# ChessComputer.net
KiCad netlist of a schematic drawn in EAGLE
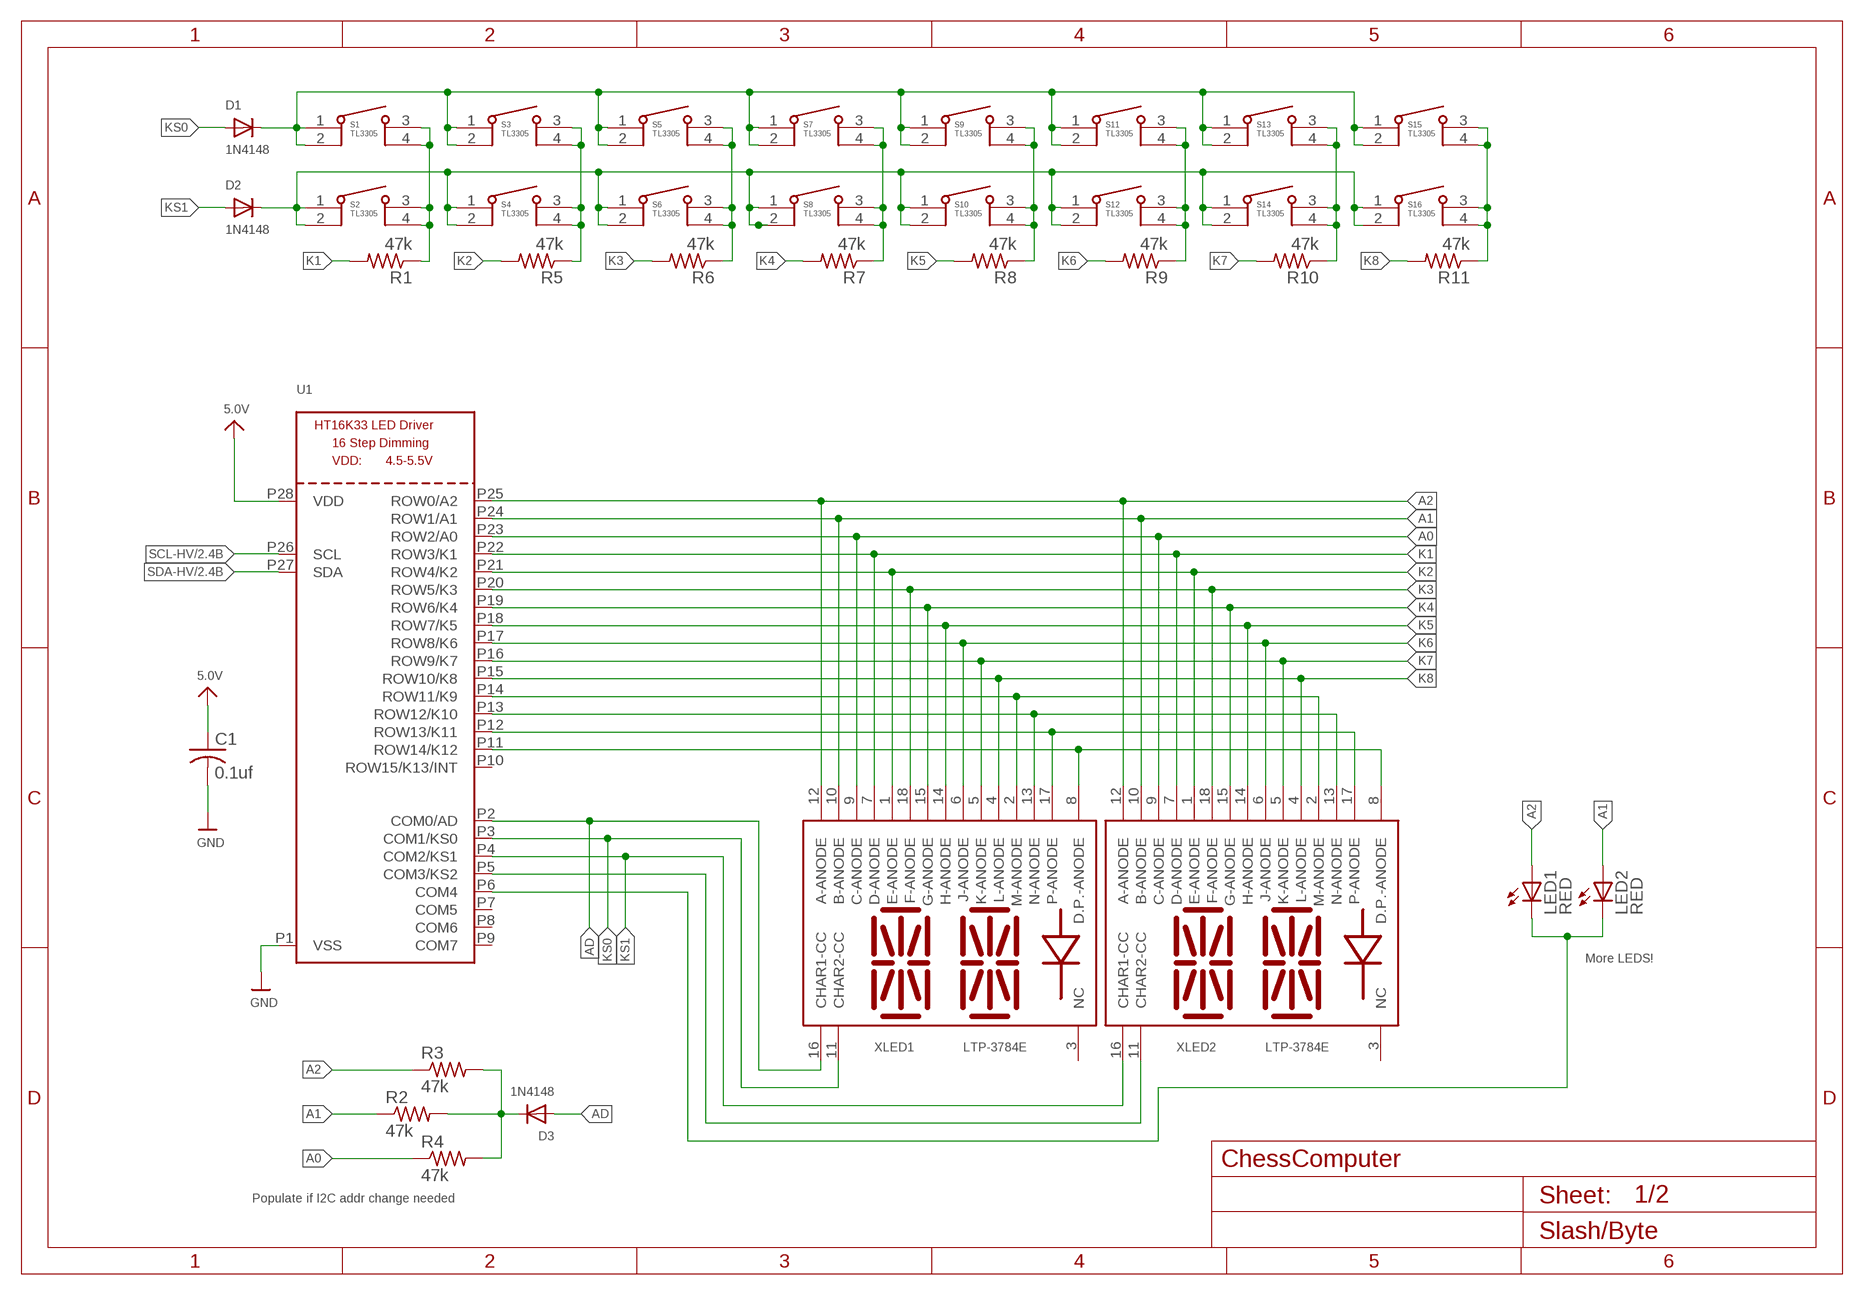
[diagram p0: schematic, sheet 1]
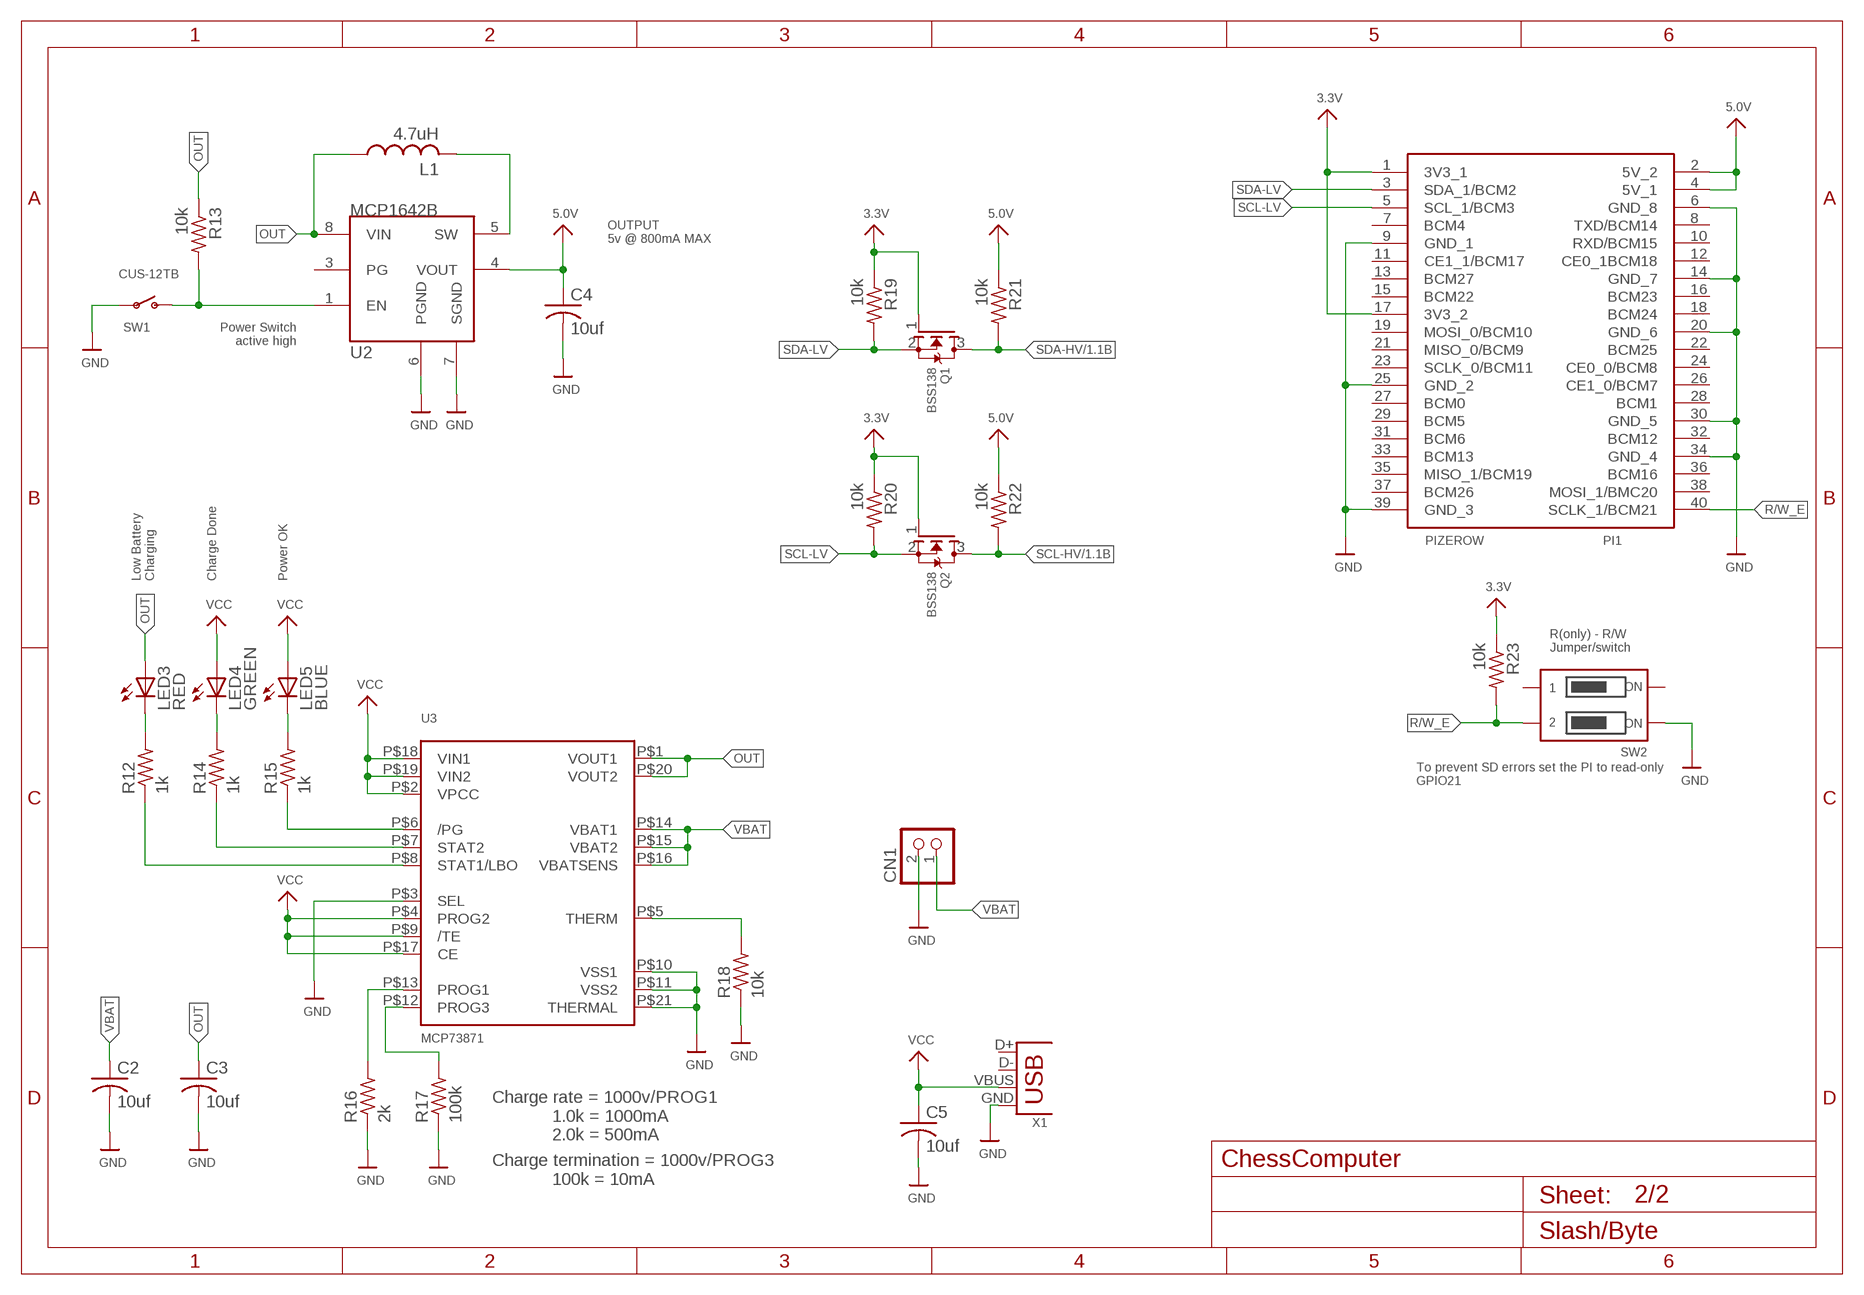
[diagram p1: schematic, sheet 2]

(export (version "E")
  (design (tool "Eeschema 10.0.6"))
  (components
    (comp (ref "C2")
      (value "10uf")
      (footprint "eagle-import:C0805K")
      (libsource (lib "eagle-import") (part "C-USC0805K"))
    )
    (comp (ref "C3")
      (value "10uf")
      (footprint "eagle-import:C0805K")
      (libsource (lib "eagle-import") (part "C-USC0805K"))
    )
    (comp (ref "C4")
      (value "10uf")
      (footprint "eagle-import:C0805K")
      (libsource (lib "eagle-import") (part "C-USC0805K"))
    )
    (comp (ref "C5")
      (value "10uf")
      (footprint "eagle-import:C0805K")
      (libsource (lib "eagle-import") (part "C-USC0805K"))
    )
    (comp (ref "CN1")
      (value "JST_2PIN-SMT-RA")
      (footprint "eagle-import:JST-PH-2-SMT-RA")
      (libsource (lib "eagle-import") (part "JST_2PIN-SMT-RA"))
    )
    (comp (ref "L1")
      (value "4.7uH")
      (footprint "eagle-import:TYS60204R7N-10")
      (libsource (lib "eagle-import") (part "TYS60204R7N-10"))
    )
    (comp (ref "LED3")
      (value "RED")
      (footprint "eagle-import:LED3MM")
      (libsource (lib "eagle-import") (part "LED3MM"))
    )
    (comp (ref "LED4")
      (value "GREEN")
      (footprint "eagle-import:LED3MM")
      (libsource (lib "eagle-import") (part "LED3MM"))
    )
    (comp (ref "LED5")
      (value "BLUE")
      (footprint "eagle-import:LED3MM")
      (libsource (lib "eagle-import") (part "LED3MM"))
    )
    (comp (ref "PI1")
      (value "PIZEROW")
      (footprint "eagle-import:RASP_PI_ZERO_BOARD_FULL")
      (libsource (lib "eagle-import") (part "PIZEROW"))
    )
    (comp (ref "Q1")
      (value "BSS138")
      (footprint "eagle-import:SOT23-R")
      (libsource (lib "eagle-import") (part "MOSFET-NREFLOW"))
    )
    (comp (ref "Q2")
      (value "BSS138")
      (footprint "eagle-import:SOT23-R")
      (libsource (lib "eagle-import") (part "MOSFET-NREFLOW"))
    )
    (comp (ref "R12")
      (value "1k")
      (footprint "eagle-import:M0805")
      (libsource (lib "eagle-import") (part "R-US_M0805"))
    )
    (comp (ref "R13")
      (value "10k")
      (footprint "eagle-import:M0805")
      (libsource (lib "eagle-import") (part "R-US_M0805"))
    )
    (comp (ref "R14")
      (value "1k")
      (footprint "eagle-import:M0805")
      (libsource (lib "eagle-import") (part "R-US_M0805"))
    )
    (comp (ref "R15")
      (value "1k")
      (footprint "eagle-import:M0805")
      (libsource (lib "eagle-import") (part "R-US_M0805"))
    )
    (comp (ref "R16")
      (value "2k")
      (footprint "eagle-import:M0805")
      (libsource (lib "eagle-import") (part "R-US_M0805"))
    )
    (comp (ref "R17")
      (value "100k")
      (footprint "eagle-import:M0805")
      (libsource (lib "eagle-import") (part "R-US_M0805"))
    )
    (comp (ref "R18")
      (value "10k")
      (footprint "eagle-import:M0805")
      (libsource (lib "eagle-import") (part "R-US_M0805"))
    )
    (comp (ref "R19")
      (value "10k")
      (footprint "eagle-import:M0805")
      (libsource (lib "eagle-import") (part "R-US_M0805"))
    )
    (comp (ref "R20")
      (value "10k")
      (footprint "eagle-import:M0805")
      (libsource (lib "eagle-import") (part "R-US_M0805"))
    )
    (comp (ref "R21")
      (value "10k")
      (footprint "eagle-import:M0805")
      (libsource (lib "eagle-import") (part "R-US_M0805"))
    )
    (comp (ref "R22")
      (value "10k")
      (footprint "eagle-import:M0805")
      (libsource (lib "eagle-import") (part "R-US_M0805"))
    )
    (comp (ref "R23")
      (value "10k")
      (footprint "eagle-import:M0805")
      (libsource (lib "eagle-import") (part "R-US_M0805"))
    )
    (comp (ref "SW1")
      (value "CUS-12TB")
      (footprint "eagle-import:SPST_SMT_19192")
      (libsource (lib "eagle-import") (part "SWITCH_SPST"))
    )
    (comp (ref "SW2")
      (value "DIPSWITCH_2PIN")
      (footprint "eagle-import:DIPSWITCH_2PIN")
      (libsource (lib "eagle-import") (part "DIPSWITCH_2PIN"))
    )
    (comp (ref "U2")
      (value "MCP1642B")
      (footprint "eagle-import:MSOP8")
      (libsource (lib "eagle-import") (part "MCP1642B"))
    )
    (comp (ref "U3")
      (value "MCP73871")
      (footprint "eagle-import:QFN20_4MM")
      (libsource (lib "eagle-import") (part "MCP73871"))
    )
    (comp (ref "X1")
      (value "MICRO-USB_ORIG")
      (footprint "eagle-import:DX4R005HJ5")
      (libsource (lib "eagle-import") (part "MICRO-USB_ORIG"))
    )
    (comp (ref "C1")
      (value "0.1uf")
      (footprint "eagle-import:C0805K")
      (libsource (lib "eagle-import") (part "C-USC0805K"))
    )
    (comp (ref "D1")
      (value "1N4148")
      (footprint "eagle-import:SOD-523")
      (libsource (lib "eagle-import") (part "DIODESOD-523"))
    )
    (comp (ref "D2")
      (value "1N4148")
      (footprint "eagle-import:SOD-523")
      (libsource (lib "eagle-import") (part "DIODESOD-523"))
    )
    (comp (ref "D3")
      (value "1N4148")
      (footprint "eagle-import:SOD-523")
      (libsource (lib "eagle-import") (part "DIODESOD-523"))
    )
    (comp (ref "LED1")
      (value "RED")
      (footprint "eagle-import:LED3MM")
      (libsource (lib "eagle-import") (part "LED3MM"))
    )
    (comp (ref "LED2")
      (value "RED")
      (footprint "eagle-import:LED3MM")
      (libsource (lib "eagle-import") (part "LED3MM"))
    )
    (comp (ref "R1")
      (value "47k")
      (footprint "eagle-import:M0805")
      (libsource (lib "eagle-import") (part "R-US_M0805"))
    )
    (comp (ref "R2")
      (value "47k")
      (footprint "eagle-import:M0805")
      (libsource (lib "eagle-import") (part "R-US_M0805"))
    )
    (comp (ref "R3")
      (value "47k")
      (footprint "eagle-import:M0805")
      (libsource (lib "eagle-import") (part "R-US_M0805"))
    )
    (comp (ref "R4")
      (value "47k")
      (footprint "eagle-import:M0805")
      (libsource (lib "eagle-import") (part "R-US_M0805"))
    )
    (comp (ref "R5")
      (value "47k")
      (footprint "eagle-import:M0805")
      (libsource (lib "eagle-import") (part "R-US_M0805"))
    )
    (comp (ref "R6")
      (value "47k")
      (footprint "eagle-import:M0805")
      (libsource (lib "eagle-import") (part "R-US_M0805"))
    )
    (comp (ref "R7")
      (value "47k")
      (footprint "eagle-import:M0805")
      (libsource (lib "eagle-import") (part "R-US_M0805"))
    )
    (comp (ref "R8")
      (value "47k")
      (footprint "eagle-import:M0805")
      (libsource (lib "eagle-import") (part "R-US_M0805"))
    )
    (comp (ref "R9")
      (value "47k")
      (footprint "eagle-import:M0805")
      (libsource (lib "eagle-import") (part "R-US_M0805"))
    )
    (comp (ref "R10")
      (value "47k")
      (footprint "eagle-import:M0805")
      (libsource (lib "eagle-import") (part "R-US_M0805"))
    )
    (comp (ref "R11")
      (value "47k")
      (footprint "eagle-import:M0805")
      (libsource (lib "eagle-import") (part "R-US_M0805"))
    )
    (comp (ref "S1")
      (value "TL3305")
      (footprint "eagle-import:TL3305")
      (libsource (lib "eagle-import") (part "TL3305"))
    )
    (comp (ref "S2")
      (value "TL3305")
      (footprint "eagle-import:TL3305")
      (libsource (lib "eagle-import") (part "TL3305"))
    )
    (comp (ref "S3")
      (value "TL3305")
      (footprint "eagle-import:TL3305")
      (libsource (lib "eagle-import") (part "TL3305"))
    )
    (comp (ref "S4")
      (value "TL3305")
      (footprint "eagle-import:TL3305")
      (libsource (lib "eagle-import") (part "TL3305"))
    )
    (comp (ref "S5")
      (value "TL3305")
      (footprint "eagle-import:TL3305")
      (libsource (lib "eagle-import") (part "TL3305"))
    )
    (comp (ref "S6")
      (value "TL3305")
      (footprint "eagle-import:TL3305")
      (libsource (lib "eagle-import") (part "TL3305"))
    )
    (comp (ref "S7")
      (value "TL3305")
      (footprint "eagle-import:TL3305")
      (libsource (lib "eagle-import") (part "TL3305"))
    )
    (comp (ref "S8")
      (value "TL3305")
      (footprint "eagle-import:TL3305")
      (libsource (lib "eagle-import") (part "TL3305"))
    )
    (comp (ref "S9")
      (value "TL3305")
      (footprint "eagle-import:TL3305")
      (libsource (lib "eagle-import") (part "TL3305"))
    )
    (comp (ref "S10")
      (value "TL3305")
      (footprint "eagle-import:TL3305")
      (libsource (lib "eagle-import") (part "TL3305"))
    )
    (comp (ref "S11")
      (value "TL3305")
      (footprint "eagle-import:TL3305")
      (libsource (lib "eagle-import") (part "TL3305"))
    )
    (comp (ref "S12")
      (value "TL3305")
      (footprint "eagle-import:TL3305")
      (libsource (lib "eagle-import") (part "TL3305"))
    )
    (comp (ref "S13")
      (value "TL3305")
      (footprint "eagle-import:TL3305")
      (libsource (lib "eagle-import") (part "TL3305"))
    )
    (comp (ref "S14")
      (value "TL3305")
      (footprint "eagle-import:TL3305")
      (libsource (lib "eagle-import") (part "TL3305"))
    )
    (comp (ref "S15")
      (value "TL3305")
      (footprint "eagle-import:TL3305")
      (libsource (lib "eagle-import") (part "TL3305"))
    )
    (comp (ref "S16")
      (value "TL3305")
      (footprint "eagle-import:TL3305")
      (libsource (lib "eagle-import") (part "TL3305"))
    )
    (comp (ref "U1")
      (value "HT16K33_SOP28")
      (footprint "eagle-import:SOP28_300MIL")
      (libsource (lib "eagle-import") (part "HT16K33_SOP28"))
    )
    (comp (ref "XLED1")
      (value "LTP-3784E")
      (footprint "eagle-import:TLP-3784E")
      (libsource (lib "eagle-import") (part "LTP-3784E"))
    )
    (comp (ref "XLED2")
      (value "LTP-3784E")
      (footprint "eagle-import:TLP-3784E")
      (libsource (lib "eagle-import") (part "LTP-3784E"))
    )
  )
  (nets
    (net (code "1") (name "3.3V") (class "Default")
      (node (ref "PI1") (pin "1") (pinfunction "3V3_1_1") (pintype "bidirectional"))
      (node (ref "PI1") (pin "17") (pinfunction "3V3_2_17") (pintype "bidirectional"))
      (node (ref "Q1") (pin "1") (pinfunction "G_1") (pintype "bidirectional"))
      (node (ref "Q2") (pin "1") (pinfunction "G_1") (pintype "bidirectional"))
      (node (ref "R19") (pin "1") (pinfunction "1_1") (pintype "passive"))
      (node (ref "R20") (pin "1") (pinfunction "1_1") (pintype "passive"))
      (node (ref "R23") (pin "1") (pinfunction "1_1") (pintype "passive"))
    )
    (net (code "2") (name "5.0V") (class "Default")
      (node (ref "C1") (pin "1") (pinfunction "1_1") (pintype "passive"))
      (node (ref "C4") (pin "1") (pinfunction "1_1") (pintype "passive"))
      (node (ref "PI1") (pin "2") (pinfunction "5V_2_2") (pintype "bidirectional"))
      (node (ref "PI1") (pin "4") (pinfunction "5V_1_4") (pintype "bidirectional"))
      (node (ref "R21") (pin "1") (pinfunction "1_1") (pintype "passive"))
      (node (ref "R22") (pin "1") (pinfunction "1_1") (pintype "passive"))
      (node (ref "U1") (pin "P28") (pinfunction "VDD_P28") (pintype "bidirectional"))
      (node (ref "U2") (pin "4") (pinfunction "VOUT_4") (pintype "bidirectional"))
    )
    (net (code "3") (name "A0") (class "Default")
      (node (ref "R4") (pin "1") (pinfunction "1_1") (pintype "passive"))
      (node (ref "U1") (pin "P23") (pinfunction "ROW2/A0_P23") (pintype "bidirectional"))
      (node (ref "XLED1") (pin "9") (pinfunction "C-ANODE_9") (pintype "bidirectional"))
      (node (ref "XLED2") (pin "9") (pinfunction "C-ANODE_9") (pintype "bidirectional"))
    )
    (net (code "4") (name "A1") (class "Default")
      (node (ref "LED2") (pin "A") (pinfunction "A_A") (pintype "passive"))
      (node (ref "R2") (pin "1") (pinfunction "1_1") (pintype "passive"))
      (node (ref "U1") (pin "P24") (pinfunction "ROW1/A1_P24") (pintype "bidirectional"))
      (node (ref "XLED1") (pin "10") (pinfunction "B-ANODE_10") (pintype "bidirectional"))
      (node (ref "XLED2") (pin "10") (pinfunction "B-ANODE_10") (pintype "bidirectional"))
    )
    (net (code "5") (name "A2") (class "Default")
      (node (ref "LED1") (pin "A") (pinfunction "A_A") (pintype "passive"))
      (node (ref "R3") (pin "1") (pinfunction "1_1") (pintype "passive"))
      (node (ref "U1") (pin "P25") (pinfunction "ROW0/A2_P25") (pintype "bidirectional"))
      (node (ref "XLED1") (pin "12") (pinfunction "A-ANODE_12") (pintype "bidirectional"))
      (node (ref "XLED2") (pin "12") (pinfunction "A-ANODE_12") (pintype "bidirectional"))
    )
    (net (code "6") (name "AD") (class "Default")
      (node (ref "D3") (pin "A") (pinfunction "A_A") (pintype "passive"))
      (node (ref "U1") (pin "P2") (pinfunction "COM0/AD_P2") (pintype "bidirectional"))
      (node (ref "XLED1") (pin "16") (pinfunction "CHAR1-CC_16") (pintype "bidirectional"))
    )
    (net (code "7") (name "GND") (class "Default")
      (node (ref "C1") (pin "2") (pinfunction "2_2") (pintype "passive"))
      (node (ref "C2") (pin "2") (pinfunction "2_2") (pintype "passive"))
      (node (ref "C3") (pin "2") (pinfunction "2_2") (pintype "passive"))
      (node (ref "C4") (pin "2") (pinfunction "2_2") (pintype "passive"))
      (node (ref "C5") (pin "2") (pinfunction "2_2") (pintype "passive"))
      (node (ref "CN1") (pin "2") (pinfunction "1_2") (pintype "passive"))
      (node (ref "PI1") (pin "14") (pinfunction "GND_7_14") (pintype "bidirectional"))
      (node (ref "PI1") (pin "20") (pinfunction "GND_6_20") (pintype "bidirectional"))
      (node (ref "PI1") (pin "25") (pinfunction "GND_2_25") (pintype "bidirectional"))
      (node (ref "PI1") (pin "30") (pinfunction "GND_5_30") (pintype "bidirectional"))
      (node (ref "PI1") (pin "34") (pinfunction "GND_4_34") (pintype "bidirectional"))
      (node (ref "PI1") (pin "39") (pinfunction "GND_3_39") (pintype "bidirectional"))
      (node (ref "PI1") (pin "6") (pinfunction "GND_8_6") (pintype "bidirectional"))
      (node (ref "PI1") (pin "9") (pinfunction "GND_1_9") (pintype "bidirectional"))
      (node (ref "R16") (pin "1") (pinfunction "1_1") (pintype "passive"))
      (node (ref "R17") (pin "1") (pinfunction "1_1") (pintype "passive"))
      (node (ref "R18") (pin "1") (pinfunction "1_1") (pintype "passive"))
      (node (ref "SW1") (pin "B") (pinfunction "P_B") (pintype "passive"))
      (node (ref "SW2") (pin "1A") (pinfunction "1A_1A") (pintype "bidirectional"))
      (node (ref "U1") (pin "P1") (pinfunction "VSS_P1") (pintype "bidirectional"))
      (node (ref "U2") (pin "6") (pinfunction "PGND_6") (pintype "bidirectional"))
      (node (ref "U2") (pin "7") (pinfunction "SGND_7") (pintype "bidirectional"))
      (node (ref "U3") (pin "P$10") (pinfunction "VSS1_P$10") (pintype "bidirectional"))
      (node (ref "U3") (pin "P$11") (pinfunction "VSS2_P$11") (pintype "bidirectional"))
      (node (ref "U3") (pin "P$21") (pinfunction "THERMAL_P$21") (pintype "bidirectional"))
      (node (ref "U3") (pin "P$3") (pinfunction "SEL_P$3") (pintype "bidirectional"))
      (node (ref "X1") (pin "GND") (pinfunction "GND_GND") (pintype "bidirectional"))
    )
    (net (code "8") (name "K1") (class "Default")
      (node (ref "R1") (pin "2") (pinfunction "2_2") (pintype "passive"))
      (node (ref "U1") (pin "P22") (pinfunction "ROW3/K1_P22") (pintype "bidirectional"))
      (node (ref "XLED1") (pin "7") (pinfunction "D-ANODE_7") (pintype "bidirectional"))
      (node (ref "XLED2") (pin "7") (pinfunction "D-ANODE_7") (pintype "bidirectional"))
    )
    (net (code "9") (name "K2") (class "Default")
      (node (ref "R5") (pin "2") (pinfunction "2_2") (pintype "passive"))
      (node (ref "U1") (pin "P21") (pinfunction "ROW4/K2_P21") (pintype "bidirectional"))
      (node (ref "XLED1") (pin "1") (pinfunction "E-ANODE_1") (pintype "bidirectional"))
      (node (ref "XLED2") (pin "1") (pinfunction "E-ANODE_1") (pintype "bidirectional"))
    )
    (net (code "10") (name "K3") (class "Default")
      (node (ref "R6") (pin "2") (pinfunction "2_2") (pintype "passive"))
      (node (ref "U1") (pin "P20") (pinfunction "ROW5/K3_P20") (pintype "bidirectional"))
      (node (ref "XLED1") (pin "18") (pinfunction "F-ANODE_18") (pintype "bidirectional"))
      (node (ref "XLED2") (pin "18") (pinfunction "F-ANODE_18") (pintype "bidirectional"))
    )
    (net (code "11") (name "K4") (class "Default")
      (node (ref "R7") (pin "2") (pinfunction "2_2") (pintype "passive"))
      (node (ref "U1") (pin "P19") (pinfunction "ROW6/K4_P19") (pintype "bidirectional"))
      (node (ref "XLED1") (pin "15") (pinfunction "G-ANODE_15") (pintype "bidirectional"))
      (node (ref "XLED2") (pin "15") (pinfunction "G-ANODE_15") (pintype "bidirectional"))
    )
    (net (code "12") (name "K5") (class "Default")
      (node (ref "R8") (pin "2") (pinfunction "2_2") (pintype "passive"))
      (node (ref "U1") (pin "P18") (pinfunction "ROW7/K5_P18") (pintype "bidirectional"))
      (node (ref "XLED1") (pin "14") (pinfunction "H-ANODE_14") (pintype "bidirectional"))
      (node (ref "XLED2") (pin "14") (pinfunction "H-ANODE_14") (pintype "bidirectional"))
    )
    (net (code "13") (name "K6") (class "Default")
      (node (ref "R9") (pin "2") (pinfunction "2_2") (pintype "passive"))
      (node (ref "U1") (pin "P17") (pinfunction "ROW8/K6_P17") (pintype "bidirectional"))
      (node (ref "XLED1") (pin "6") (pinfunction "J-ANODE_6") (pintype "bidirectional"))
      (node (ref "XLED2") (pin "6") (pinfunction "J-ANODE_6") (pintype "bidirectional"))
    )
    (net (code "14") (name "K7") (class "Default")
      (node (ref "R10") (pin "2") (pinfunction "2_2") (pintype "passive"))
      (node (ref "U1") (pin "P16") (pinfunction "ROW9/K7_P16") (pintype "bidirectional"))
      (node (ref "XLED1") (pin "5") (pinfunction "K-ANODE_5") (pintype "bidirectional"))
      (node (ref "XLED2") (pin "5") (pinfunction "K-ANODE_5") (pintype "bidirectional"))
    )
    (net (code "15") (name "K8") (class "Default")
      (node (ref "R11") (pin "2") (pinfunction "2_2") (pintype "passive"))
      (node (ref "U1") (pin "P15") (pinfunction "ROW10/K8_P15") (pintype "bidirectional"))
      (node (ref "XLED1") (pin "4") (pinfunction "L-ANODE_4") (pintype "bidirectional"))
      (node (ref "XLED2") (pin "4") (pinfunction "L-ANODE_4") (pintype "bidirectional"))
    )
    (net (code "16") (name "KS0") (class "Default")
      (node (ref "D1") (pin "A") (pinfunction "A_A") (pintype "passive"))
      (node (ref "U1") (pin "P3") (pinfunction "COM1/KS0_P3") (pintype "bidirectional"))
      (node (ref "XLED1") (pin "11") (pinfunction "CHAR2-CC_11") (pintype "bidirectional"))
    )
    (net (code "17") (name "KS1") (class "Default")
      (node (ref "D2") (pin "A") (pinfunction "A_A") (pintype "passive"))
      (node (ref "U1") (pin "P4") (pinfunction "COM2/KS1_P4") (pintype "bidirectional"))
      (node (ref "XLED2") (pin "16") (pinfunction "CHAR1-CC_16") (pintype "bidirectional"))
    )
    (net (code "18") (name "Net-(D1-C)") (class "Default")
      (node (ref "D1") (pin "K") (pinfunction "C_K") (pintype "passive"))
      (node (ref "S1") (pin "1") (pinfunction "1_1") (pintype "bidirectional"))
      (node (ref "S1") (pin "2") (pinfunction "2_2") (pintype "bidirectional"))
      (node (ref "S11") (pin "1") (pinfunction "1_1") (pintype "bidirectional"))
      (node (ref "S11") (pin "2") (pinfunction "2_2") (pintype "bidirectional"))
      (node (ref "S13") (pin "1") (pinfunction "1_1") (pintype "bidirectional"))
      (node (ref "S13") (pin "2") (pinfunction "2_2") (pintype "bidirectional"))
      (node (ref "S15") (pin "1") (pinfunction "1_1") (pintype "bidirectional"))
      (node (ref "S15") (pin "2") (pinfunction "2_2") (pintype "bidirectional"))
      (node (ref "S3") (pin "1") (pinfunction "1_1") (pintype "bidirectional"))
      (node (ref "S3") (pin "2") (pinfunction "2_2") (pintype "bidirectional"))
      (node (ref "S5") (pin "1") (pinfunction "1_1") (pintype "bidirectional"))
      (node (ref "S5") (pin "2") (pinfunction "2_2") (pintype "bidirectional"))
      (node (ref "S7") (pin "1") (pinfunction "1_1") (pintype "bidirectional"))
      (node (ref "S7") (pin "2") (pinfunction "2_2") (pintype "bidirectional"))
      (node (ref "S9") (pin "1") (pinfunction "1_1") (pintype "bidirectional"))
      (node (ref "S9") (pin "2") (pinfunction "2_2") (pintype "bidirectional"))
    )
    (net (code "19") (name "Net-(D2-C)") (class "Default")
      (node (ref "D2") (pin "K") (pinfunction "C_K") (pintype "passive"))
      (node (ref "S10") (pin "1") (pinfunction "1_1") (pintype "bidirectional"))
      (node (ref "S10") (pin "2") (pinfunction "2_2") (pintype "bidirectional"))
      (node (ref "S12") (pin "1") (pinfunction "1_1") (pintype "bidirectional"))
      (node (ref "S12") (pin "2") (pinfunction "2_2") (pintype "bidirectional"))
      (node (ref "S14") (pin "1") (pinfunction "1_1") (pintype "bidirectional"))
      (node (ref "S14") (pin "2") (pinfunction "2_2") (pintype "bidirectional"))
      (node (ref "S16") (pin "1") (pinfunction "1_1") (pintype "bidirectional"))
      (node (ref "S16") (pin "2") (pinfunction "2_2") (pintype "bidirectional"))
      (node (ref "S2") (pin "1") (pinfunction "1_1") (pintype "bidirectional"))
      (node (ref "S2") (pin "2") (pinfunction "2_2") (pintype "bidirectional"))
      (node (ref "S4") (pin "1") (pinfunction "1_1") (pintype "bidirectional"))
      (node (ref "S4") (pin "2") (pinfunction "2_2") (pintype "bidirectional"))
      (node (ref "S6") (pin "1") (pinfunction "1_1") (pintype "bidirectional"))
      (node (ref "S6") (pin "2") (pinfunction "2_2") (pintype "bidirectional"))
      (node (ref "S8") (pin "1") (pinfunction "1_1") (pintype "bidirectional"))
      (node (ref "S8") (pin "2") (pinfunction "2_2") (pintype "bidirectional"))
    )
    (net (code "20") (name "Net-(D3-C)") (class "Default")
      (node (ref "D3") (pin "K") (pinfunction "C_K") (pintype "passive"))
      (node (ref "R2") (pin "2") (pinfunction "2_2") (pintype "passive"))
      (node (ref "R3") (pin "2") (pinfunction "2_2") (pintype "passive"))
      (node (ref "R4") (pin "2") (pinfunction "2_2") (pintype "passive"))
    )
    (net (code "21") (name "Net-(L1-2)") (class "Default")
      (node (ref "L1") (pin "P$2") (pinfunction "2_P$2") (pintype "passive"))
      (node (ref "U2") (pin "5") (pinfunction "SW_5") (pintype "bidirectional"))
    )
    (net (code "22") (name "Net-(LED1-C)") (class "Default")
      (node (ref "LED1") (pin "K") (pinfunction "C_K") (pintype "passive"))
      (node (ref "LED2") (pin "K") (pinfunction "C_K") (pintype "passive"))
      (node (ref "U1") (pin "P6") (pinfunction "COM4_P6") (pintype "bidirectional"))
    )
    (net (code "23") (name "Net-(LED3-C)") (class "Default")
      (node (ref "LED3") (pin "K") (pinfunction "C_K") (pintype "passive"))
      (node (ref "R12") (pin "2") (pinfunction "2_2") (pintype "passive"))
    )
    (net (code "24") (name "Net-(LED4-C)") (class "Default")
      (node (ref "LED4") (pin "K") (pinfunction "C_K") (pintype "passive"))
      (node (ref "R14") (pin "2") (pinfunction "2_2") (pintype "passive"))
    )
    (net (code "25") (name "Net-(LED5-C)") (class "Default")
      (node (ref "LED5") (pin "K") (pinfunction "C_K") (pintype "passive"))
      (node (ref "R15") (pin "2") (pinfunction "2_2") (pintype "passive"))
    )
    (net (code "26") (name "Net-(R1-Pad1)") (class "Default")
      (node (ref "R1") (pin "1") (pinfunction "1_1") (pintype "passive"))
      (node (ref "S1") (pin "3") (pinfunction "3_3") (pintype "bidirectional"))
      (node (ref "S1") (pin "4") (pinfunction "4_4") (pintype "bidirectional"))
      (node (ref "S2") (pin "3") (pinfunction "3_3") (pintype "bidirectional"))
      (node (ref "S2") (pin "4") (pinfunction "4_4") (pintype "bidirectional"))
    )
    (net (code "27") (name "Net-(R5-Pad1)") (class "Default")
      (node (ref "R5") (pin "1") (pinfunction "1_1") (pintype "passive"))
      (node (ref "S3") (pin "3") (pinfunction "3_3") (pintype "bidirectional"))
      (node (ref "S3") (pin "4") (pinfunction "4_4") (pintype "bidirectional"))
      (node (ref "S4") (pin "3") (pinfunction "3_3") (pintype "bidirectional"))
      (node (ref "S4") (pin "4") (pinfunction "4_4") (pintype "bidirectional"))
    )
    (net (code "28") (name "Net-(R6-Pad1)") (class "Default")
      (node (ref "R6") (pin "1") (pinfunction "1_1") (pintype "passive"))
      (node (ref "S5") (pin "3") (pinfunction "3_3") (pintype "bidirectional"))
      (node (ref "S5") (pin "4") (pinfunction "4_4") (pintype "bidirectional"))
      (node (ref "S6") (pin "3") (pinfunction "3_3") (pintype "bidirectional"))
      (node (ref "S6") (pin "4") (pinfunction "4_4") (pintype "bidirectional"))
    )
    (net (code "29") (name "Net-(R7-Pad1)") (class "Default")
      (node (ref "R7") (pin "1") (pinfunction "1_1") (pintype "passive"))
      (node (ref "S7") (pin "3") (pinfunction "3_3") (pintype "bidirectional"))
      (node (ref "S7") (pin "4") (pinfunction "4_4") (pintype "bidirectional"))
      (node (ref "S8") (pin "3") (pinfunction "3_3") (pintype "bidirectional"))
      (node (ref "S8") (pin "4") (pinfunction "4_4") (pintype "bidirectional"))
    )
    (net (code "30") (name "Net-(R8-Pad1)") (class "Default")
      (node (ref "R8") (pin "1") (pinfunction "1_1") (pintype "passive"))
      (node (ref "S10") (pin "3") (pinfunction "3_3") (pintype "bidirectional"))
      (node (ref "S10") (pin "4") (pinfunction "4_4") (pintype "bidirectional"))
      (node (ref "S9") (pin "3") (pinfunction "3_3") (pintype "bidirectional"))
      (node (ref "S9") (pin "4") (pinfunction "4_4") (pintype "bidirectional"))
    )
    (net (code "31") (name "Net-(R9-Pad1)") (class "Default")
      (node (ref "R9") (pin "1") (pinfunction "1_1") (pintype "passive"))
      (node (ref "S11") (pin "3") (pinfunction "3_3") (pintype "bidirectional"))
      (node (ref "S11") (pin "4") (pinfunction "4_4") (pintype "bidirectional"))
      (node (ref "S12") (pin "3") (pinfunction "3_3") (pintype "bidirectional"))
      (node (ref "S12") (pin "4") (pinfunction "4_4") (pintype "bidirectional"))
    )
    (net (code "32") (name "Net-(R10-Pad1)") (class "Default")
      (node (ref "R10") (pin "1") (pinfunction "1_1") (pintype "passive"))
      (node (ref "S13") (pin "3") (pinfunction "3_3") (pintype "bidirectional"))
      (node (ref "S13") (pin "4") (pinfunction "4_4") (pintype "bidirectional"))
      (node (ref "S14") (pin "3") (pinfunction "3_3") (pintype "bidirectional"))
      (node (ref "S14") (pin "4") (pinfunction "4_4") (pintype "bidirectional"))
    )
    (net (code "33") (name "Net-(R11-Pad1)") (class "Default")
      (node (ref "R11") (pin "1") (pinfunction "1_1") (pintype "passive"))
      (node (ref "S15") (pin "3") (pinfunction "3_3") (pintype "bidirectional"))
      (node (ref "S15") (pin "4") (pinfunction "4_4") (pintype "bidirectional"))
      (node (ref "S16") (pin "3") (pinfunction "3_3") (pintype "bidirectional"))
      (node (ref "S16") (pin "4") (pinfunction "4_4") (pintype "bidirectional"))
    )
    (net (code "34") (name "Net-(SW1-S)") (class "Default")
      (node (ref "R13") (pin "2") (pinfunction "2_2") (pintype "passive"))
      (node (ref "SW1") (pin "C") (pinfunction "S_C") (pintype "passive"))
      (node (ref "U2") (pin "1") (pinfunction "EN_1") (pintype "bidirectional"))
    )
    (net (code "35") (name "Net-(U1-COM3{slash}KS2)") (class "Default")
      (node (ref "U1") (pin "P5") (pinfunction "COM3/KS2_P5") (pintype "bidirectional"))
      (node (ref "XLED2") (pin "11") (pinfunction "CHAR2-CC_11") (pintype "bidirectional"))
    )
    (net (code "36") (name "Net-(U1-ROW11{slash}K9)") (class "Default")
      (node (ref "U1") (pin "P14") (pinfunction "ROW11/K9_P14") (pintype "bidirectional"))
      (node (ref "XLED1") (pin "2") (pinfunction "M-ANODE_2") (pintype "bidirectional"))
      (node (ref "XLED2") (pin "2") (pinfunction "M-ANODE_2") (pintype "bidirectional"))
    )
    (net (code "37") (name "Net-(U1-ROW12{slash}K10)") (class "Default")
      (node (ref "U1") (pin "P13") (pinfunction "ROW12/K10_P13") (pintype "bidirectional"))
      (node (ref "XLED1") (pin "13") (pinfunction "N-ANODE_13") (pintype "bidirectional"))
      (node (ref "XLED2") (pin "13") (pinfunction "N-ANODE_13") (pintype "bidirectional"))
    )
    (net (code "38") (name "Net-(U1-ROW13{slash}K11)") (class "Default")
      (node (ref "U1") (pin "P12") (pinfunction "ROW13/K11_P12") (pintype "bidirectional"))
      (node (ref "XLED1") (pin "17") (pinfunction "P-ANODE_17") (pintype "bidirectional"))
      (node (ref "XLED2") (pin "17") (pinfunction "P-ANODE_17") (pintype "bidirectional"))
    )
    (net (code "39") (name "Net-(U1-ROW14{slash}K12)") (class "Default")
      (node (ref "U1") (pin "P11") (pinfunction "ROW14/K12_P11") (pintype "bidirectional"))
      (node (ref "XLED1") (pin "8") (pinfunction "D.P.-ANODE_8") (pintype "bidirectional"))
      (node (ref "XLED2") (pin "8") (pinfunction "D.P.-ANODE_8") (pintype "bidirectional"))
    )
    (net (code "40") (name "Net-(U3-PROG1)") (class "Default")
      (node (ref "R16") (pin "2") (pinfunction "2_2") (pintype "passive"))
      (node (ref "U3") (pin "P$13") (pinfunction "PROG1_P$13") (pintype "bidirectional"))
    )
    (net (code "41") (name "Net-(U3-PROG3)") (class "Default")
      (node (ref "R17") (pin "2") (pinfunction "2_2") (pintype "passive"))
      (node (ref "U3") (pin "P$12") (pinfunction "PROG3_P$12") (pintype "bidirectional"))
    )
    (net (code "42") (name "Net-(U3-STAT1{slash}LBO)") (class "Default")
      (node (ref "R12") (pin "1") (pinfunction "1_1") (pintype "passive"))
      (node (ref "U3") (pin "P$8") (pinfunction "STAT1/LBO_P$8") (pintype "bidirectional"))
    )
    (net (code "43") (name "Net-(U3-STAT2)") (class "Default")
      (node (ref "R14") (pin "1") (pinfunction "1_1") (pintype "passive"))
      (node (ref "U3") (pin "P$7") (pinfunction "STAT2_P$7") (pintype "bidirectional"))
    )
    (net (code "44") (name "Net-(U3-THERM)") (class "Default")
      (node (ref "R18") (pin "2") (pinfunction "2_2") (pintype "passive"))
      (node (ref "U3") (pin "P$5") (pinfunction "THERM_P$5") (pintype "bidirectional"))
    )
    (net (code "45") (name "Net-(U3-{slash}PG)") (class "Default")
      (node (ref "R15") (pin "1") (pinfunction "1_1") (pintype "passive"))
      (node (ref "U3") (pin "P$6") (pinfunction "/PG_P$6") (pintype "bidirectional"))
    )
    (net (code "46") (name "OUT") (class "Default")
      (node (ref "C3") (pin "1") (pinfunction "1_1") (pintype "passive"))
      (node (ref "L1") (pin "P$1") (pinfunction "1_P$1") (pintype "passive"))
      (node (ref "LED3") (pin "A") (pinfunction "A_A") (pintype "passive"))
      (node (ref "R13") (pin "1") (pinfunction "1_1") (pintype "passive"))
      (node (ref "U2") (pin "8") (pinfunction "VIN_8") (pintype "bidirectional"))
      (node (ref "U3") (pin "P$1") (pinfunction "VOUT1_P$1") (pintype "bidirectional"))
      (node (ref "U3") (pin "P$20") (pinfunction "VOUT2_P$20") (pintype "bidirectional"))
    )
    (net (code "47") (name "R{slash}W_E") (class "Default")
      (node (ref "PI1") (pin "40") (pinfunction "SCLK_1/BCM21_40") (pintype "bidirectional"))
      (node (ref "R23") (pin "2") (pinfunction "2_2") (pintype "passive"))
      (node (ref "SW2") (pin "1B") (pinfunction "1B_1B") (pintype "bidirectional"))
    )
    (net (code "48") (name "SCL-HV") (class "Default")
      (node (ref "Q2") (pin "3") (pinfunction "D_3") (pintype "bidirectional"))
      (node (ref "R22") (pin "2") (pinfunction "2_2") (pintype "passive"))
      (node (ref "U1") (pin "P26") (pinfunction "SCL_P26") (pintype "bidirectional"))
    )
    (net (code "49") (name "SCL-LV") (class "Default")
      (node (ref "PI1") (pin "5") (pinfunction "SCL_1/BCM3_5") (pintype "bidirectional"))
      (node (ref "Q2") (pin "2") (pinfunction "S_2") (pintype "bidirectional"))
      (node (ref "R20") (pin "2") (pinfunction "2_2") (pintype "passive"))
    )
    (net (code "50") (name "SDA-HV") (class "Default")
      (node (ref "Q1") (pin "3") (pinfunction "D_3") (pintype "bidirectional"))
      (node (ref "R21") (pin "2") (pinfunction "2_2") (pintype "passive"))
      (node (ref "U1") (pin "P27") (pinfunction "SDA_P27") (pintype "bidirectional"))
    )
    (net (code "51") (name "SDA-LV") (class "Default")
      (node (ref "PI1") (pin "3") (pinfunction "SDA_1/BCM2_3") (pintype "bidirectional"))
      (node (ref "Q1") (pin "2") (pinfunction "S_2") (pintype "bidirectional"))
      (node (ref "R19") (pin "2") (pinfunction "2_2") (pintype "passive"))
    )
    (net (code "52") (name "VBAT") (class "Default")
      (node (ref "C2") (pin "1") (pinfunction "1_1") (pintype "passive"))
      (node (ref "CN1") (pin "1") (pinfunction "2_1") (pintype "passive"))
      (node (ref "U3") (pin "P$14") (pinfunction "VBAT1_P$14") (pintype "bidirectional"))
      (node (ref "U3") (pin "P$15") (pinfunction "VBAT2_P$15") (pintype "bidirectional"))
      (node (ref "U3") (pin "P$16") (pinfunction "VBATSENS_P$16") (pintype "bidirectional"))
    )
    (net (code "53") (name "VCC") (class "Default")
      (node (ref "C5") (pin "1") (pinfunction "1_1") (pintype "passive"))
      (node (ref "LED4") (pin "A") (pinfunction "A_A") (pintype "passive"))
      (node (ref "LED5") (pin "A") (pinfunction "A_A") (pintype "passive"))
      (node (ref "U3") (pin "P$17") (pinfunction "CE_P$17") (pintype "bidirectional"))
      (node (ref "U3") (pin "P$18") (pinfunction "VIN1_P$18") (pintype "bidirectional"))
      (node (ref "U3") (pin "P$19") (pinfunction "VIN2_P$19") (pintype "bidirectional"))
      (node (ref "U3") (pin "P$2") (pinfunction "VPCC_P$2") (pintype "bidirectional"))
      (node (ref "U3") (pin "P$4") (pinfunction "PROG2_P$4") (pintype "bidirectional"))
      (node (ref "U3") (pin "P$9") (pinfunction "/TE_P$9") (pintype "bidirectional"))
      (node (ref "X1") (pin "VBUS") (pinfunction "VBUS_VBUS") (pintype "bidirectional"))
    )
    (net (code "54") (name "unconnected-(PI1-BCM0-Pad27)") (class "Default")
      (node (ref "PI1") (pin "27") (pinfunction "BCM0_27") (pintype "bidirectional"))
    )
    (net (code "55") (name "unconnected-(PI1-BCM1-Pad28)") (class "Default")
      (node (ref "PI1") (pin "28") (pinfunction "BCM1_28") (pintype "bidirectional"))
    )
    (net (code "56") (name "unconnected-(PI1-BCM4-Pad7)") (class "Default")
      (node (ref "PI1") (pin "7") (pinfunction "BCM4_7") (pintype "bidirectional"))
    )
    (net (code "57") (name "unconnected-(PI1-BCM5-Pad29)") (class "Default")
      (node (ref "PI1") (pin "29") (pinfunction "BCM5_29") (pintype "bidirectional"))
    )
    (net (code "58") (name "unconnected-(PI1-BCM6-Pad31)") (class "Default")
      (node (ref "PI1") (pin "31") (pinfunction "BCM6_31") (pintype "bidirectional"))
    )
    (net (code "59") (name "unconnected-(PI1-BCM12-Pad32)") (class "Default")
      (node (ref "PI1") (pin "32") (pinfunction "BCM12_32") (pintype "bidirectional"))
    )
    (net (code "60") (name "unconnected-(PI1-BCM13-Pad33)") (class "Default")
      (node (ref "PI1") (pin "33") (pinfunction "BCM13_33") (pintype "bidirectional"))
    )
    (net (code "61") (name "unconnected-(PI1-BCM16-Pad36)") (class "Default")
      (node (ref "PI1") (pin "36") (pinfunction "BCM16_36") (pintype "bidirectional"))
    )
    (net (code "62") (name "unconnected-(PI1-BCM22-Pad15)") (class "Default")
      (node (ref "PI1") (pin "15") (pinfunction "BCM22_15") (pintype "bidirectional"))
    )
    (net (code "63") (name "unconnected-(PI1-BCM23-Pad16)") (class "Default")
      (node (ref "PI1") (pin "16") (pinfunction "BCM23_16") (pintype "bidirectional"))
    )
    (net (code "64") (name "unconnected-(PI1-BCM24-Pad18)") (class "Default")
      (node (ref "PI1") (pin "18") (pinfunction "BCM24_18") (pintype "bidirectional"))
    )
    (net (code "65") (name "unconnected-(PI1-BCM25-Pad22)") (class "Default")
      (node (ref "PI1") (pin "22") (pinfunction "BCM25_22") (pintype "bidirectional"))
    )
    (net (code "66") (name "unconnected-(PI1-BCM26-Pad37)") (class "Default")
      (node (ref "PI1") (pin "37") (pinfunction "BCM26_37") (pintype "bidirectional"))
    )
    (net (code "67") (name "unconnected-(PI1-BCM27-Pad13)") (class "Default")
      (node (ref "PI1") (pin "13") (pinfunction "BCM27_13") (pintype "bidirectional"))
    )
    (net (code "68") (name "unconnected-(PI1-CE0_0{slash}BCM8-Pad24)") (class "Default")
      (node (ref "PI1") (pin "24") (pinfunction "CE0_0/BCM8_24") (pintype "bidirectional"))
    )
    (net (code "69") (name "unconnected-(PI1-CE0_1BCM18-Pad12)") (class "Default")
      (node (ref "PI1") (pin "12") (pinfunction "CE0_1BCM18_12") (pintype "bidirectional"))
    )
    (net (code "70") (name "unconnected-(PI1-CE1_0{slash}BCM7-Pad26)") (class "Default")
      (node (ref "PI1") (pin "26") (pinfunction "CE1_0/BCM7_26") (pintype "bidirectional"))
    )
    (net (code "71") (name "unconnected-(PI1-CE1_1{slash}BCM17-Pad11)") (class "Default")
      (node (ref "PI1") (pin "11") (pinfunction "CE1_1/BCM17_11") (pintype "bidirectional"))
    )
    (net (code "72") (name "unconnected-(PI1-MISO_0{slash}BCM9-Pad21)") (class "Default")
      (node (ref "PI1") (pin "21") (pinfunction "MISO_0/BCM9_21") (pintype "bidirectional"))
    )
    (net (code "73") (name "unconnected-(PI1-MISO_1{slash}BCM19-Pad35)") (class "Default")
      (node (ref "PI1") (pin "35") (pinfunction "MISO_1/BCM19_35") (pintype "bidirectional"))
    )
    (net (code "74") (name "unconnected-(PI1-MOSI_0{slash}BCM10-Pad19)") (class "Default")
      (node (ref "PI1") (pin "19") (pinfunction "MOSI_0/BCM10_19") (pintype "bidirectional"))
    )
    (net (code "75") (name "unconnected-(PI1-MOSI_1{slash}BMC20-Pad38)") (class "Default")
      (node (ref "PI1") (pin "38") (pinfunction "MOSI_1/BMC20_38") (pintype "bidirectional"))
    )
    (net (code "76") (name "unconnected-(PI1-RXD{slash}BCM15-Pad10)") (class "Default")
      (node (ref "PI1") (pin "10") (pinfunction "RXD/BCM15_10") (pintype "bidirectional"))
    )
    (net (code "77") (name "unconnected-(PI1-SCLK_0{slash}BCM11-Pad23)") (class "Default")
      (node (ref "PI1") (pin "23") (pinfunction "SCLK_0/BCM11_23") (pintype "bidirectional"))
    )
    (net (code "78") (name "unconnected-(PI1-TXD{slash}BCM14-Pad8)") (class "Default")
      (node (ref "PI1") (pin "8") (pinfunction "TXD/BCM14_8") (pintype "bidirectional"))
    )
    (net (code "79") (name "unconnected-(SW2-Pad2A)") (class "Default")
      (node (ref "SW2") (pin "2A") (pinfunction "2A_2A") (pintype "bidirectional"))
    )
    (net (code "80") (name "unconnected-(SW2-Pad2B)") (class "Default")
      (node (ref "SW2") (pin "2B") (pinfunction "2B_2B") (pintype "bidirectional"))
    )
    (net (code "81") (name "unconnected-(U1-COM5-PadP7)") (class "Default")
      (node (ref "U1") (pin "P7") (pinfunction "COM5_P7") (pintype "bidirectional"))
    )
    (net (code "82") (name "unconnected-(U1-COM6-PadP8)") (class "Default")
      (node (ref "U1") (pin "P8") (pinfunction "COM6_P8") (pintype "bidirectional"))
    )
    (net (code "83") (name "unconnected-(U1-COM7-PadP9)") (class "Default")
      (node (ref "U1") (pin "P9") (pinfunction "COM7_P9") (pintype "bidirectional"))
    )
    (net (code "84") (name "unconnected-(U1-ROW15{slash}K13{slash}INT-PadP10)") (class "Default")
      (node (ref "U1") (pin "P10") (pinfunction "ROW15/K13/INT_P10") (pintype "bidirectional"))
    )
    (net (code "85") (name "unconnected-(U2-PG-Pad3)") (class "Default")
      (node (ref "U2") (pin "3") (pinfunction "PG_3") (pintype "bidirectional"))
    )
    (net (code "86") (name "unconnected-(X1-PadD+)") (class "Default")
      (node (ref "X1") (pin "D+") (pinfunction "D+_D+") (pintype "bidirectional"))
    )
    (net (code "87") (name "unconnected-(X1-PadD-)") (class "Default")
      (node (ref "X1") (pin "D-") (pinfunction "D-_D-") (pintype "bidirectional"))
    )
    (net (code "88") (name "unconnected-(XLED1-NC-Pad3)") (class "Default")
      (node (ref "XLED1") (pin "3") (pinfunction "NC_3") (pintype "bidirectional"))
    )
    (net (code "89") (name "unconnected-(XLED2-NC-Pad3)") (class "Default")
      (node (ref "XLED2") (pin "3") (pinfunction "NC_3") (pintype "bidirectional"))
    )
  )
)
